# switches.net
KiCad netlist of a schematic drawn in Altium Designer
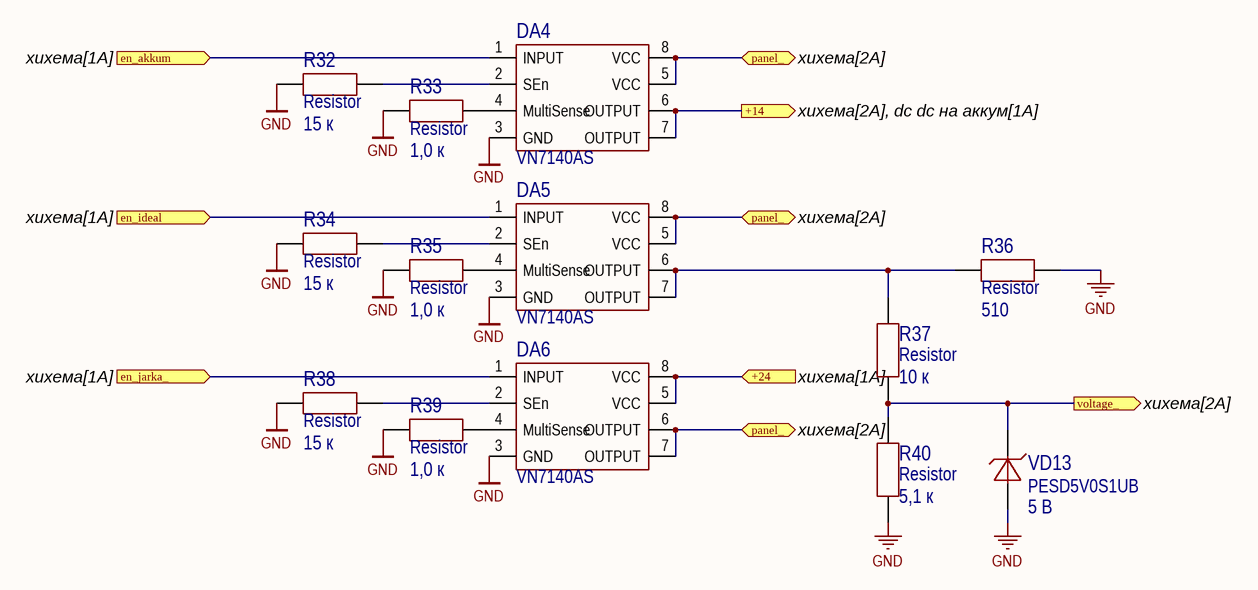
[diagram p0: switches.SchDoc]

(export (version "E")
  (design (tool "Eeschema 10.0.6"))
  (components
    (comp (ref "DA4")
      (value "VN7140AS")
      (footprint "SOP8")
      (description "Силовой ключ верхнего плеча с аналоговой обратной связью MultiSense автомобильного применения")
      (libsource (lib "Hydrolib") (part "VN7140AS"))
    )
    (comp (ref "DA5")
      (value "VN7140AS")
      (footprint "SOP8")
      (description "Силовой ключ верхнего плеча с аналоговой обратной связью MultiSense автомобильного применения")
      (libsource (lib "Hydrolib") (part "VN7140AS"))
    )
    (comp (ref "DA6")
      (value "VN7140AS")
      (footprint "SOP8")
      (description "Силовой ключ верхнего плеча с аналоговой обратной связью MultiSense автомобильного применения")
      (libsource (lib "Hydrolib") (part "VN7140AS"))
    )
    (comp (ref "R32")
      (value "Resistor")
      (footprint "0603R")
      (description "Резистор номиналом 15 кОм и точностью 1%")
      (fields
        (field (name "ALTIUM_VALUE") "15 к")
        (field (name "PART NUMBER") "Resistor_15k_1_0603")
        (field (name "TOLERANCE") "1%")
      )
      (libsource (lib "Hydrolib") (part "Resistor"))
    )
    (comp (ref "R33")
      (value "Resistor")
      (footprint "0603R")
      (description "Резистор номиналом 1,0 кОм и точностью 1%")
      (fields
        (field (name "ALTIUM_VALUE") "1,0 к")
        (field (name "PART NUMBER") "Resistor_1.0k_1_0603")
        (field (name "TOLERANCE") "1%")
      )
      (libsource (lib "Hydrolib") (part "Resistor"))
    )
    (comp (ref "R34")
      (value "Resistor")
      (footprint "0603R")
      (description "Резистор номиналом 15 кОм и точностью 1%")
      (fields
        (field (name "ALTIUM_VALUE") "15 к")
        (field (name "PART NUMBER") "Resistor_15k_1_0603")
        (field (name "TOLERANCE") "1%")
      )
      (libsource (lib "Hydrolib") (part "Resistor"))
    )
    (comp (ref "R35")
      (value "Resistor")
      (footprint "0603R")
      (description "Резистор номиналом 1,0 кОм и точностью 1%")
      (fields
        (field (name "ALTIUM_VALUE") "1,0 к")
        (field (name "PART NUMBER") "Resistor_1.0k_1_0603")
        (field (name "TOLERANCE") "1%")
      )
      (libsource (lib "Hydrolib") (part "Resistor"))
    )
    (comp (ref "R36")
      (value "Resistor")
      (footprint "2512R")
      (description "Резистор номиналом 510 Ом и точностью 1%")
      (fields
        (field (name "ALTIUM_VALUE") "510")
        (field (name "PART NUMBER") "Resistor_510_1_0603")
        (field (name "TOLERANCE") "1%")
      )
      (libsource (lib "Hydrolib") (part "Resistor"))
    )
    (comp (ref "R37")
      (value "Resistor")
      (footprint "0603R")
      (description "Резистор номиналом 10 кОм и точностью 1%")
      (fields
        (field (name "ALTIUM_VALUE") "10 к")
        (field (name "PART NUMBER") "Resistor_10k_1_0603")
        (field (name "TOLERANCE") "1%")
      )
      (libsource (lib "") (part "Resistor_1"))
    )
    (comp (ref "R38")
      (value "Resistor")
      (footprint "0603R")
      (description "Резистор номиналом 15 кОм и точностью 1%")
      (fields
        (field (name "ALTIUM_VALUE") "15 к")
        (field (name "PART NUMBER") "Resistor_15k_1_0603")
        (field (name "TOLERANCE") "1%")
      )
      (libsource (lib "Hydrolib") (part "Resistor"))
    )
    (comp (ref "R39")
      (value "Resistor")
      (footprint "0603R")
      (description "Резистор номиналом 1,0 кОм и точностью 1%")
      (fields
        (field (name "ALTIUM_VALUE") "1,0 к")
        (field (name "PART NUMBER") "Resistor_1.0k_1_0603")
        (field (name "TOLERANCE") "1%")
      )
      (libsource (lib "Hydrolib") (part "Resistor"))
    )
    (comp (ref "R40")
      (value "Resistor")
      (footprint "0603R")
      (description "Резистор номиналом 5,1 кОм и точностью 1%")
      (fields
        (field (name "ALTIUM_VALUE") "5,1 к")
        (field (name "PART NUMBER") "Resistor_5.1k_1_0603")
        (field (name "TOLERANCE") "1%")
      )
      (libsource (lib "") (part "Resistor_1"))
    )
    (comp (ref "VD13")
      (value "PESD5V0S1UB")
      (footprint "SOD523")
      (description "Защитный диод на 5 В, рассеиваемая мощность 330 Вт")
      (fields (field (name "ALTIUM_VALUE") "5 В"))
      (libsource (lib "Hydrolib") (part "TVS_1_1dir"))
    )
  )
  (nets
    (net (code "1") (name "/+14") (class "Default")
      (node (ref "DA4") (pin "6") (pinfunction "OUTPUT_6") (pintype "passive"))
      (node (ref "DA4") (pin "7") (pinfunction "OUTPUT_7") (pintype "passive"))
    )
    (net (code "2") (name "/+24") (class "Default")
      (node (ref "DA6") (pin "5") (pinfunction "VCC_5") (pintype "passive"))
      (node (ref "DA6") (pin "8") (pinfunction "VCC_8") (pintype "passive"))
    )
    (net (code "3") (name "/en_akkum") (class "Default")
      (node (ref "DA4") (pin "1") (pinfunction "INPUT_1") (pintype "passive"))
    )
    (net (code "4") (name "/en_ideal") (class "Default")
      (node (ref "DA5") (pin "1") (pinfunction "INPUT_1") (pintype "passive"))
    )
    (net (code "5") (name "/en_jarka_") (class "Default")
      (node (ref "DA6") (pin "1") (pinfunction "INPUT_1") (pintype "passive"))
    )
    (net (code "6") (name "/panel_") (class "Default")
      (node (ref "DA4") (pin "5") (pinfunction "VCC_5") (pintype "passive"))
      (node (ref "DA4") (pin "8") (pinfunction "VCC_8") (pintype "passive"))
      (node (ref "DA5") (pin "5") (pinfunction "VCC_5") (pintype "passive"))
      (node (ref "DA5") (pin "8") (pinfunction "VCC_8") (pintype "passive"))
      (node (ref "DA6") (pin "6") (pinfunction "OUTPUT_6") (pintype "passive"))
      (node (ref "DA6") (pin "7") (pinfunction "OUTPUT_7") (pintype "passive"))
    )
    (net (code "7") (name "/voltage_") (class "Default")
      (node (ref "R37") (pin "1") (pinfunction "1_1") (pintype "passive"))
      (node (ref "R40") (pin "2") (pinfunction "2_2") (pintype "passive"))
      (node (ref "VD13") (pin "2") (pinfunction "2_2") (pintype "passive"))
    )
    (net (code "8") (name "GND") (class "Default")
      (node (ref "DA4") (pin "3") (pinfunction "GND_3") (pintype "passive"))
      (node (ref "DA5") (pin "3") (pinfunction "GND_3") (pintype "passive"))
      (node (ref "DA6") (pin "3") (pinfunction "GND_3") (pintype "passive"))
      (node (ref "R32") (pin "1") (pinfunction "1_1") (pintype "passive"))
      (node (ref "R33") (pin "1") (pinfunction "1_1") (pintype "passive"))
      (node (ref "R34") (pin "1") (pinfunction "1_1") (pintype "passive"))
      (node (ref "R35") (pin "1") (pinfunction "1_1") (pintype "passive"))
      (node (ref "R36") (pin "2") (pinfunction "2_2") (pintype "passive"))
      (node (ref "R38") (pin "1") (pinfunction "1_1") (pintype "passive"))
      (node (ref "R39") (pin "1") (pinfunction "1_1") (pintype "passive"))
      (node (ref "R40") (pin "1") (pinfunction "1_1") (pintype "passive"))
      (node (ref "VD13") (pin "1") (pinfunction "1_1") (pintype "passive"))
    )
    (net (code "9") (name "Net-(DA4-MultiSense)") (class "Default")
      (node (ref "DA4") (pin "4") (pinfunction "MultiSense_4") (pintype "passive"))
      (node (ref "R33") (pin "2") (pinfunction "2_2") (pintype "passive"))
    )
    (net (code "10") (name "Net-(DA4-SEn)") (class "Default")
      (node (ref "DA4") (pin "2") (pinfunction "SEn_2") (pintype "passive"))
      (node (ref "R32") (pin "2") (pinfunction "2_2") (pintype "passive"))
    )
    (net (code "11") (name "Net-(DA5-MultiSense)") (class "Default")
      (node (ref "DA5") (pin "4") (pinfunction "MultiSense_4") (pintype "passive"))
      (node (ref "R35") (pin "2") (pinfunction "2_2") (pintype "passive"))
    )
    (net (code "12") (name "Net-(DA5-OUTPUT-Pad6)") (class "Default")
      (node (ref "DA5") (pin "6") (pinfunction "OUTPUT_6") (pintype "passive"))
      (node (ref "DA5") (pin "7") (pinfunction "OUTPUT_7") (pintype "passive"))
      (node (ref "R36") (pin "1") (pinfunction "1_1") (pintype "passive"))
      (node (ref "R37") (pin "2") (pinfunction "2_2") (pintype "passive"))
    )
    (net (code "13") (name "Net-(DA5-SEn)") (class "Default")
      (node (ref "DA5") (pin "2") (pinfunction "SEn_2") (pintype "passive"))
      (node (ref "R34") (pin "2") (pinfunction "2_2") (pintype "passive"))
    )
    (net (code "14") (name "Net-(DA6-MultiSense)") (class "Default")
      (node (ref "DA6") (pin "4") (pinfunction "MultiSense_4") (pintype "passive"))
      (node (ref "R39") (pin "2") (pinfunction "2_2") (pintype "passive"))
    )
    (net (code "15") (name "Net-(DA6-SEn)") (class "Default")
      (node (ref "DA6") (pin "2") (pinfunction "SEn_2") (pintype "passive"))
      (node (ref "R38") (pin "2") (pinfunction "2_2") (pintype "passive"))
    )
  )
)
